# core.net
KiCad netlist of a schematic drawn in Altium Designer
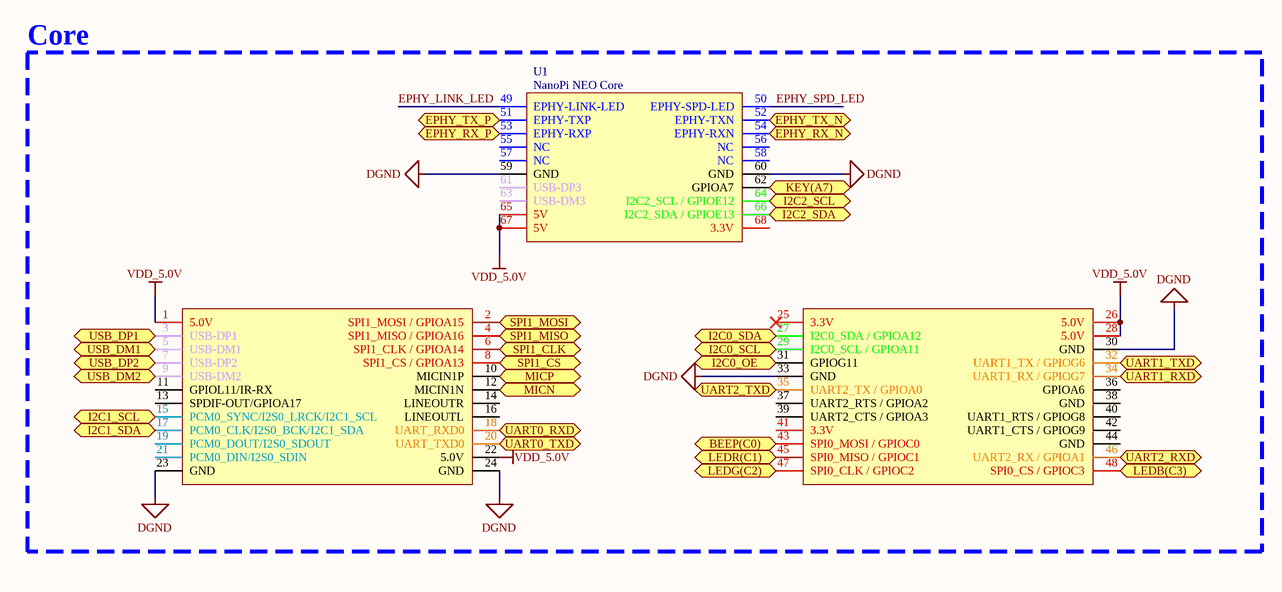
[diagram p0: core.SchDoc]

(export (version "E")
  (design (tool "Eeschema 10.0.6"))
  (components
    (comp (ref "U1")
      (value "NanoPi NEO Core")
      (footprint "NanoPi NEO Core")
      (libsource (lib "集大电协1.5") (part "NanoPi NEO Core"))
    )
  )
  (nets
    (net (code "1") (name "/BEEP(C0)") (class "Default")
      (node (ref "U1") (pin "43") (pinfunction "SPI0_MOSI_/_GPIOC0_43") (pintype "passive"))
    )
    (net (code "2") (name "/EPHY_LINK_LED") (class "Default")
      (node (ref "U1") (pin "49") (pinfunction "EPHY-LINK-LED_49") (pintype "passive"))
    )
    (net (code "3") (name "/EPHY_RX_N") (class "Default")
      (node (ref "U1") (pin "54") (pinfunction "EPHY-RXN_54") (pintype "passive"))
    )
    (net (code "4") (name "/EPHY_RX_P") (class "Default")
      (node (ref "U1") (pin "53") (pinfunction "EPHY-RXP_53") (pintype "passive"))
    )
    (net (code "5") (name "/EPHY_SPD_LED") (class "Default")
      (node (ref "U1") (pin "50") (pinfunction "EPHY-SPD-LED_50") (pintype "passive"))
    )
    (net (code "6") (name "/EPHY_TX_N") (class "Default")
      (node (ref "U1") (pin "52") (pinfunction "EPHY-TXN_52") (pintype "passive"))
    )
    (net (code "7") (name "/EPHY_TX_P") (class "Default")
      (node (ref "U1") (pin "51") (pinfunction "EPHY-TXP_51") (pintype "passive"))
    )
    (net (code "8") (name "/I2C0_OE") (class "Default")
      (node (ref "U1") (pin "31") (pinfunction "GPIOG11_31") (pintype "passive"))
    )
    (net (code "9") (name "/I2C0_SCL") (class "Default")
      (node (ref "U1") (pin "29") (pinfunction "I2C0_SCL_/_GPIOA11_29") (pintype "passive"))
    )
    (net (code "10") (name "/I2C0_SDA") (class "Default")
      (node (ref "U1") (pin "27") (pinfunction "I2C0_SDA_/_GPIOA12_27") (pintype "passive"))
    )
    (net (code "11") (name "/I2C1_SCL") (class "Default")
      (node (ref "U1") (pin "15") (pinfunction "PCM0_SYNC/I2S0_LRCK/I2C1_SCL_15") (pintype "passive"))
    )
    (net (code "12") (name "/I2C1_SDA") (class "Default")
      (node (ref "U1") (pin "17") (pinfunction "PCM0_CLK/I2S0_BCK/I2C1_SDA_17") (pintype "passive"))
    )
    (net (code "13") (name "/I2C2_SCL") (class "Default")
      (node (ref "U1") (pin "64") (pinfunction "I2C2_SCL_/_GPIOE12_64") (pintype "passive"))
    )
    (net (code "14") (name "/I2C2_SDA") (class "Default")
      (node (ref "U1") (pin "66") (pinfunction "I2C2_SDA_/_GPIOE13_66") (pintype "passive"))
    )
    (net (code "15") (name "/KEY(A7)") (class "Default")
      (node (ref "U1") (pin "62") (pinfunction "GPIOA7_62") (pintype "passive"))
    )
    (net (code "16") (name "/LEDB(C3)") (class "Default")
      (node (ref "U1") (pin "48") (pinfunction "SPI0_CS_/_GPIOC3_48") (pintype "passive"))
    )
    (net (code "17") (name "/LEDG(C2)") (class "Default")
      (node (ref "U1") (pin "47") (pinfunction "SPI0_CLK_/_GPIOC2_47") (pintype "passive"))
    )
    (net (code "18") (name "/LEDR(C1)") (class "Default")
      (node (ref "U1") (pin "45") (pinfunction "SPI0_MISO_/_GPIOC1_45") (pintype "passive"))
    )
    (net (code "19") (name "/MICN") (class "Default")
      (node (ref "U1") (pin "12") (pinfunction "MICIN1N_12") (pintype "passive"))
    )
    (net (code "20") (name "/MICP") (class "Default")
      (node (ref "U1") (pin "10") (pinfunction "MICIN1P_10") (pintype "passive"))
    )
    (net (code "21") (name "/SPI1_CLK") (class "Default")
      (node (ref "U1") (pin "6") (pinfunction "SPI1_CLK_/_GPIOA14_6") (pintype "passive"))
    )
    (net (code "22") (name "/SPI1_CS") (class "Default")
      (node (ref "U1") (pin "8") (pinfunction "SPI1_CS_/_GPIOA13_8") (pintype "passive"))
    )
    (net (code "23") (name "/SPI1_MISO") (class "Default")
      (node (ref "U1") (pin "4") (pinfunction "SPI1_MISO_/_GPIOA16_4") (pintype "passive"))
    )
    (net (code "24") (name "/SPI1_MOSI") (class "Default")
      (node (ref "U1") (pin "2") (pinfunction "SPI1_MOSI_/_GPIOA15_2") (pintype "passive"))
    )
    (net (code "25") (name "/UART0_RXD") (class "Default")
      (node (ref "U1") (pin "18") (pinfunction "UART_RXD0_18") (pintype "passive"))
    )
    (net (code "26") (name "/UART0_TXD") (class "Default")
      (node (ref "U1") (pin "20") (pinfunction "UART_TXD0_20") (pintype "passive"))
    )
    (net (code "27") (name "/UART1_RXD") (class "Default")
      (node (ref "U1") (pin "34") (pinfunction "UART1_RX_/_GPIOG7_34") (pintype "passive"))
    )
    (net (code "28") (name "/UART1_TXD") (class "Default")
      (node (ref "U1") (pin "32") (pinfunction "UART1_TX_/_GPIOG6_32") (pintype "passive"))
    )
    (net (code "29") (name "/UART2_RXD") (class "Default")
      (node (ref "U1") (pin "46") (pinfunction "UART2_RX_/_GPIOA1_46") (pintype "passive"))
    )
    (net (code "30") (name "/UART2_TXD") (class "Default")
      (node (ref "U1") (pin "35") (pinfunction "UART2_TX_/_GPIOA0_35") (pintype "passive"))
    )
    (net (code "31") (name "/USB_DM1") (class "Default")
      (node (ref "U1") (pin "5") (pinfunction "USB-DM1_5") (pintype "passive"))
    )
    (net (code "32") (name "/USB_DM2") (class "Default")
      (node (ref "U1") (pin "9") (pinfunction "USB-DM2_9") (pintype "passive"))
    )
    (net (code "33") (name "/USB_DP1") (class "Default")
      (node (ref "U1") (pin "3") (pinfunction "USB-DP1_3") (pintype "passive"))
    )
    (net (code "34") (name "/USB_DP2") (class "Default")
      (node (ref "U1") (pin "7") (pinfunction "USB-DP2_7") (pintype "passive"))
    )
    (net (code "35") (name "DGND") (class "Default")
      (node (ref "U1") (pin "23") (pinfunction "GND_23") (pintype "passive"))
      (node (ref "U1") (pin "24") (pinfunction "GND_24") (pintype "passive"))
      (node (ref "U1") (pin "30") (pinfunction "GND_30") (pintype "passive"))
      (node (ref "U1") (pin "33") (pinfunction "GND_33") (pintype "passive"))
      (node (ref "U1") (pin "59") (pinfunction "GND_59") (pintype "passive"))
      (node (ref "U1") (pin "60") (pinfunction "GND_60") (pintype "passive"))
    )
    (net (code "36") (name "VDD_5.0V") (class "Default")
      (node (ref "U1") (pin "1") (pinfunction "5.0V_1") (pintype "passive"))
      (node (ref "U1") (pin "22") (pinfunction "5.0V_22") (pintype "passive"))
      (node (ref "U1") (pin "26") (pinfunction "5.0V_26") (pintype "passive"))
      (node (ref "U1") (pin "28") (pinfunction "5.0V_28") (pintype "passive"))
      (node (ref "U1") (pin "65") (pinfunction "5V_65") (pintype "passive"))
      (node (ref "U1") (pin "67") (pinfunction "5V_67") (pintype "passive"))
    )
    (net (code "37") (name "unconnected-(U1-3.3V-Pad25)") (class "Default")
      (node (ref "U1") (pin "25") (pinfunction "3.3V_25") (pintype "passive+no_connect"))
    )
    (net (code "38") (name "unconnected-(U1-3.3V-Pad41)") (class "Default")
      (node (ref "U1") (pin "41") (pinfunction "3.3V_41") (pintype "passive"))
    )
    (net (code "39") (name "unconnected-(U1-3.3V-Pad68)") (class "Default")
      (node (ref "U1") (pin "68") (pinfunction "3.3V_68") (pintype "passive"))
    )
    (net (code "40") (name "unconnected-(U1-GND-Pad38)") (class "Default")
      (node (ref "U1") (pin "38") (pinfunction "GND_38") (pintype "passive"))
    )
    (net (code "41") (name "unconnected-(U1-GND-Pad44)") (class "Default")
      (node (ref "U1") (pin "44") (pinfunction "GND_44") (pintype "passive"))
    )
    (net (code "42") (name "unconnected-(U1-GPIOA6-Pad36)") (class "Default")
      (node (ref "U1") (pin "36") (pinfunction "GPIOA6_36") (pintype "passive"))
    )
    (net (code "43") (name "unconnected-(U1-GPIOL11{slash}IR-RX-Pad11)") (class "Default")
      (node (ref "U1") (pin "11") (pinfunction "GPIOL11/IR-RX_11") (pintype "passive"))
    )
    (net (code "44") (name "unconnected-(U1-LINEOUTL-Pad16)") (class "Default")
      (node (ref "U1") (pin "16") (pinfunction "LINEOUTL_16") (pintype "passive"))
    )
    (net (code "45") (name "unconnected-(U1-LINEOUTR-Pad14)") (class "Default")
      (node (ref "U1") (pin "14") (pinfunction "LINEOUTR_14") (pintype "passive"))
    )
    (net (code "46") (name "unconnected-(U1-NC-Pad55)") (class "Default")
      (node (ref "U1") (pin "55") (pinfunction "NC_55") (pintype "passive"))
    )
    (net (code "47") (name "unconnected-(U1-NC-Pad56)") (class "Default")
      (node (ref "U1") (pin "56") (pinfunction "NC_56") (pintype "passive"))
    )
    (net (code "48") (name "unconnected-(U1-NC-Pad57)") (class "Default")
      (node (ref "U1") (pin "57") (pinfunction "NC_57") (pintype "passive"))
    )
    (net (code "49") (name "unconnected-(U1-NC-Pad58)") (class "Default")
      (node (ref "U1") (pin "58") (pinfunction "NC_58") (pintype "passive"))
    )
    (net (code "50") (name "unconnected-(U1-PCM0_DIN{slash}I2S0_SDIN-Pad21)") (class "Default")
      (node (ref "U1") (pin "21") (pinfunction "PCM0_DIN/I2S0_SDIN_21") (pintype "passive"))
    )
    (net (code "51") (name "unconnected-(U1-PCM0_DOUT{slash}I2S0_SDOUT-Pad19)") (class "Default")
      (node (ref "U1") (pin "19") (pinfunction "PCM0_DOUT/I2S0_SDOUT_19") (pintype "passive"))
    )
    (net (code "52") (name "unconnected-(U1-SPDIF-OUT{slash}GPIOA17-Pad13)") (class "Default")
      (node (ref "U1") (pin "13") (pinfunction "SPDIF-OUT/GPIOA17_13") (pintype "passive"))
    )
    (net (code "53") (name "unconnected-(U1-UART1_CTS_{slash}_GPIOG9-Pad42)") (class "Default")
      (node (ref "U1") (pin "42") (pinfunction "UART1_CTS_/_GPIOG9_42") (pintype "passive"))
    )
    (net (code "54") (name "unconnected-(U1-UART1_RTS_{slash}_GPIOG8-Pad40)") (class "Default")
      (node (ref "U1") (pin "40") (pinfunction "UART1_RTS_/_GPIOG8_40") (pintype "passive"))
    )
    (net (code "55") (name "unconnected-(U1-UART2_CTS_{slash}_GPIOA3-Pad39)") (class "Default")
      (node (ref "U1") (pin "39") (pinfunction "UART2_CTS_/_GPIOA3_39") (pintype "passive"))
    )
    (net (code "56") (name "unconnected-(U1-UART2_RTS_{slash}_GPIOA2-Pad37)") (class "Default")
      (node (ref "U1") (pin "37") (pinfunction "UART2_RTS_/_GPIOA2_37") (pintype "passive"))
    )
    (net (code "57") (name "unconnected-(U1-USB-DM3-Pad63)") (class "Default")
      (node (ref "U1") (pin "63") (pinfunction "USB-DM3_63") (pintype "passive"))
    )
    (net (code "58") (name "unconnected-(U1-USB-DP3-Pad61)") (class "Default")
      (node (ref "U1") (pin "61") (pinfunction "USB-DP3_61") (pintype "passive"))
    )
  )
)
